# lcd_brd.net
KiCad netlist of a schematic drawn in EAGLE
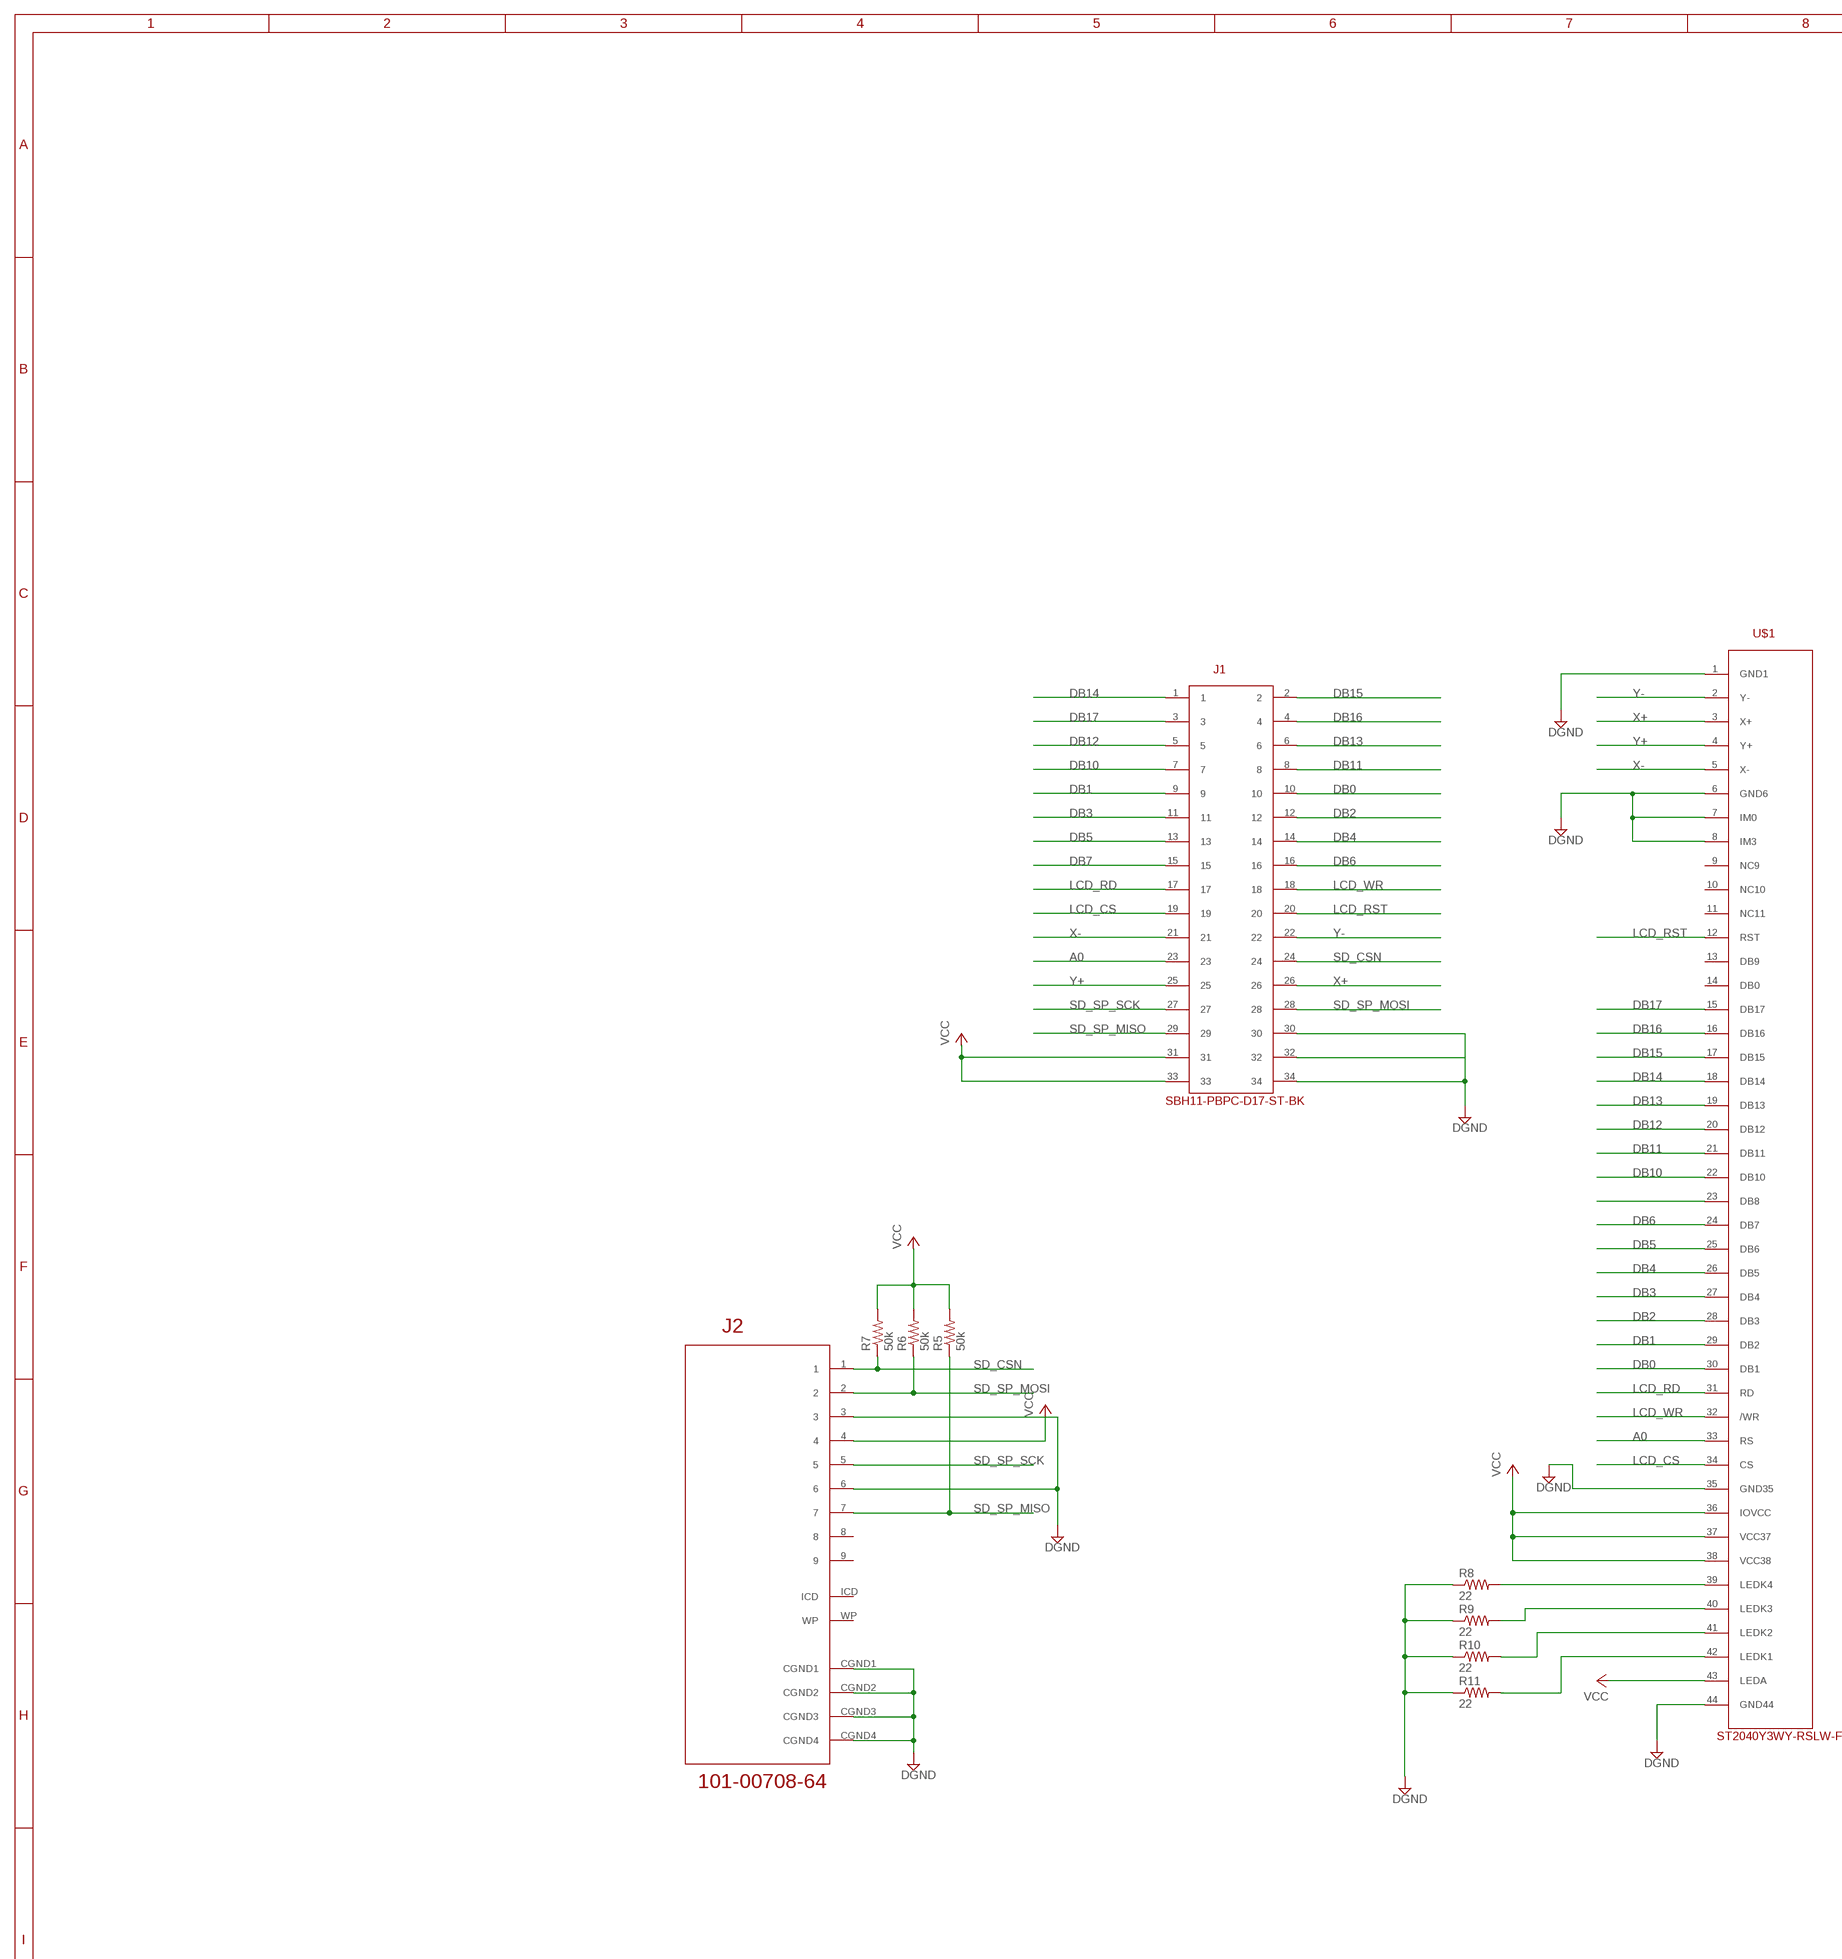
[diagram p0: schematic, sheet 1, part 1 of 2]
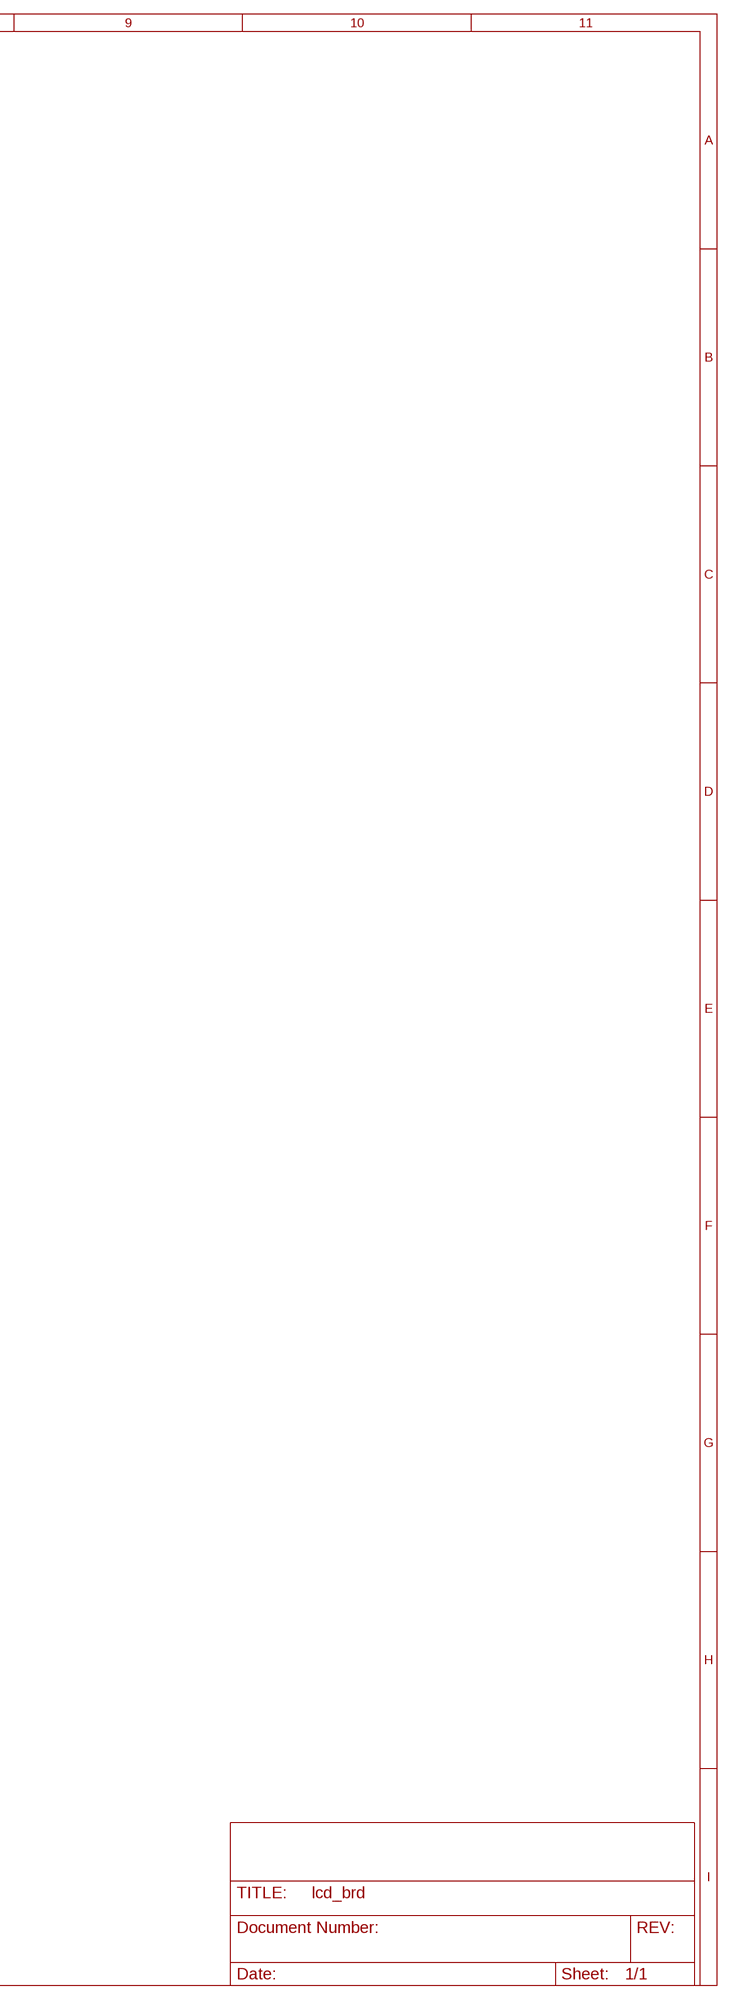
[diagram p1: schematic, sheet 1, part 2 of 2]

(export (version "E")
  (design (tool "Eeschema 10.0.6"))
  (components
    (comp (ref "J1")
      (value "SBH11-PBPC-D17-ST-BK")
      (footprint "eagle-import:SBH11-PBPC-D17-ST-BK")
      (libsource (lib "eagle-import") (part "SBH11-PBPC-D17-ST-BK"))
    )
    (comp (ref "J2")
      (value "101-00708-64")
      (footprint "eagle-import:101-00708-64")
      (libsource (lib "eagle-import") (part "101-00708-64"))
    )
    (comp (ref "R5")
      (value "50k")
      (footprint "eagle-import:R0603")
      (libsource (lib "eagle-import") (part "R-US_R0603"))
    )
    (comp (ref "R6")
      (value "50k")
      (footprint "eagle-import:R0603")
      (libsource (lib "eagle-import") (part "R-US_R0603"))
    )
    (comp (ref "R7")
      (value "50k")
      (footprint "eagle-import:R0603")
      (libsource (lib "eagle-import") (part "R-US_R0603"))
    )
    (comp (ref "R8")
      (value "22")
      (footprint "eagle-import:R0603")
      (libsource (lib "eagle-import") (part "R-US_R0603"))
    )
    (comp (ref "R9")
      (value "22")
      (footprint "eagle-import:R0603")
      (libsource (lib "eagle-import") (part "R-US_R0603"))
    )
    (comp (ref "R10")
      (value "22")
      (footprint "eagle-import:R0603")
      (libsource (lib "eagle-import") (part "R-US_R0603"))
    )
    (comp (ref "R11")
      (value "22")
      (footprint "eagle-import:R0603")
      (libsource (lib "eagle-import") (part "R-US_R0603"))
    )
    (comp (ref "U$1")
      (value "ST2040Y3WY-RSLW-F")
      (footprint "eagle-import:ST0240Y3WY-RSLW-F")
      (libsource (lib "eagle-import") (part "ST2040Y3WY-RSLW-F"))
    )
  )
  (nets
    (net (code "1") (name "/A0") (class "Default")
      (node (ref "J1") (pin "23") (pinfunction "23_23") (pintype "bidirectional"))
      (node (ref "U$1") (pin "33") (pinfunction "RS_33") (pintype "bidirectional"))
    )
    (net (code "2") (name "/DB0") (class "Default")
      (node (ref "J1") (pin "10") (pinfunction "10_10") (pintype "bidirectional"))
      (node (ref "U$1") (pin "30") (pinfunction "DB1_30") (pintype "bidirectional"))
    )
    (net (code "3") (name "/DB1") (class "Default")
      (node (ref "J1") (pin "9") (pinfunction "9_9") (pintype "bidirectional"))
      (node (ref "U$1") (pin "29") (pinfunction "DB2_29") (pintype "bidirectional"))
    )
    (net (code "4") (name "/DB2") (class "Default")
      (node (ref "J1") (pin "12") (pinfunction "12_12") (pintype "bidirectional"))
      (node (ref "U$1") (pin "28") (pinfunction "DB3_28") (pintype "bidirectional"))
    )
    (net (code "5") (name "/DB3") (class "Default")
      (node (ref "J1") (pin "11") (pinfunction "11_11") (pintype "bidirectional"))
      (node (ref "U$1") (pin "27") (pinfunction "DB4_27") (pintype "bidirectional"))
    )
    (net (code "6") (name "/DB4") (class "Default")
      (node (ref "J1") (pin "14") (pinfunction "14_14") (pintype "bidirectional"))
      (node (ref "U$1") (pin "26") (pinfunction "DB5_26") (pintype "bidirectional"))
    )
    (net (code "7") (name "/DB5") (class "Default")
      (node (ref "J1") (pin "13") (pinfunction "13_13") (pintype "bidirectional"))
      (node (ref "U$1") (pin "25") (pinfunction "DB6_25") (pintype "bidirectional"))
    )
    (net (code "8") (name "/DB6") (class "Default")
      (node (ref "J1") (pin "16") (pinfunction "16_16") (pintype "bidirectional"))
      (node (ref "U$1") (pin "24") (pinfunction "DB7_24") (pintype "bidirectional"))
    )
    (net (code "9") (name "/DB7") (class "Default")
      (node (ref "J1") (pin "15") (pinfunction "15_15") (pintype "bidirectional"))
      (node (ref "U$1") (pin "23") (pinfunction "DB8_23") (pintype "bidirectional"))
    )
    (net (code "10") (name "/DB10") (class "Default")
      (node (ref "J1") (pin "7") (pinfunction "7_7") (pintype "bidirectional"))
      (node (ref "U$1") (pin "22") (pinfunction "DB10_22") (pintype "bidirectional"))
    )
    (net (code "11") (name "/DB11") (class "Default")
      (node (ref "J1") (pin "8") (pinfunction "8_8") (pintype "bidirectional"))
      (node (ref "U$1") (pin "21") (pinfunction "DB11_21") (pintype "bidirectional"))
    )
    (net (code "12") (name "/DB12") (class "Default")
      (node (ref "J1") (pin "5") (pinfunction "5_5") (pintype "bidirectional"))
      (node (ref "U$1") (pin "20") (pinfunction "DB12_20") (pintype "bidirectional"))
    )
    (net (code "13") (name "/DB13") (class "Default")
      (node (ref "J1") (pin "6") (pinfunction "6_6") (pintype "bidirectional"))
      (node (ref "U$1") (pin "19") (pinfunction "DB13_19") (pintype "bidirectional"))
    )
    (net (code "14") (name "/DB14") (class "Default")
      (node (ref "J1") (pin "1") (pinfunction "1_1") (pintype "bidirectional"))
      (node (ref "U$1") (pin "18") (pinfunction "DB14_18") (pintype "bidirectional"))
    )
    (net (code "15") (name "/DB15") (class "Default")
      (node (ref "J1") (pin "2") (pinfunction "2_2") (pintype "bidirectional"))
      (node (ref "U$1") (pin "17") (pinfunction "DB15_17") (pintype "bidirectional"))
    )
    (net (code "16") (name "/DB16") (class "Default")
      (node (ref "J1") (pin "4") (pinfunction "4_4") (pintype "bidirectional"))
      (node (ref "U$1") (pin "16") (pinfunction "DB16_16") (pintype "bidirectional"))
    )
    (net (code "17") (name "/DB17") (class "Default")
      (node (ref "J1") (pin "3") (pinfunction "3_3") (pintype "bidirectional"))
      (node (ref "U$1") (pin "15") (pinfunction "DB17_15") (pintype "bidirectional"))
    )
    (net (code "18") (name "/LCD_CS") (class "Default")
      (node (ref "J1") (pin "19") (pinfunction "19_19") (pintype "bidirectional"))
      (node (ref "U$1") (pin "34") (pinfunction "CS_34") (pintype "bidirectional"))
    )
    (net (code "19") (name "/LCD_RD") (class "Default")
      (node (ref "J1") (pin "17") (pinfunction "17_17") (pintype "bidirectional"))
      (node (ref "U$1") (pin "31") (pinfunction "RD_31") (pintype "bidirectional"))
    )
    (net (code "20") (name "/LCD_RST") (class "Default")
      (node (ref "J1") (pin "20") (pinfunction "20_20") (pintype "bidirectional"))
      (node (ref "U$1") (pin "12") (pinfunction "RST_12") (pintype "bidirectional"))
    )
    (net (code "21") (name "/LCD_WR") (class "Default")
      (node (ref "J1") (pin "18") (pinfunction "18_18") (pintype "bidirectional"))
      (node (ref "U$1") (pin "32") (pinfunction "/WR_32") (pintype "bidirectional"))
    )
    (net (code "22") (name "/SD_CSN") (class "Default")
      (node (ref "J1") (pin "24") (pinfunction "24_24") (pintype "bidirectional"))
      (node (ref "J2") (pin "1") (pinfunction "1_1") (pintype "bidirectional"))
      (node (ref "R7") (pin "1") (pinfunction "1_1") (pintype "passive"))
    )
    (net (code "23") (name "/SD_SP_MISO") (class "Default")
      (node (ref "J1") (pin "29") (pinfunction "29_29") (pintype "bidirectional"))
      (node (ref "J2") (pin "7") (pinfunction "7_7") (pintype "bidirectional"))
      (node (ref "R5") (pin "1") (pinfunction "1_1") (pintype "passive"))
    )
    (net (code "24") (name "/SD_SP_MOSI") (class "Default")
      (node (ref "J1") (pin "28") (pinfunction "28_28") (pintype "bidirectional"))
      (node (ref "J2") (pin "2") (pinfunction "2_2") (pintype "bidirectional"))
      (node (ref "R6") (pin "1") (pinfunction "1_1") (pintype "passive"))
    )
    (net (code "25") (name "/SD_SP_SCK") (class "Default")
      (node (ref "J1") (pin "27") (pinfunction "27_27") (pintype "bidirectional"))
      (node (ref "J2") (pin "5") (pinfunction "5_5") (pintype "bidirectional"))
    )
    (net (code "26") (name "/X+") (class "Default")
      (node (ref "J1") (pin "26") (pinfunction "26_26") (pintype "bidirectional"))
      (node (ref "U$1") (pin "3") (pinfunction "X+_3") (pintype "bidirectional"))
    )
    (net (code "27") (name "/X-") (class "Default")
      (node (ref "J1") (pin "21") (pinfunction "21_21") (pintype "bidirectional"))
      (node (ref "U$1") (pin "5") (pinfunction "X-_5") (pintype "bidirectional"))
    )
    (net (code "28") (name "/Y+") (class "Default")
      (node (ref "J1") (pin "25") (pinfunction "25_25") (pintype "bidirectional"))
      (node (ref "U$1") (pin "4") (pinfunction "Y+_4") (pintype "bidirectional"))
    )
    (net (code "29") (name "/Y-") (class "Default")
      (node (ref "J1") (pin "22") (pinfunction "22_22") (pintype "bidirectional"))
      (node (ref "U$1") (pin "2") (pinfunction "Y-_2") (pintype "bidirectional"))
    )
    (net (code "30") (name "DGND") (class "Default")
      (node (ref "J1") (pin "30") (pinfunction "30_30") (pintype "bidirectional"))
      (node (ref "J1") (pin "32") (pinfunction "32_32") (pintype "bidirectional"))
      (node (ref "J1") (pin "34") (pinfunction "34_34") (pintype "bidirectional"))
      (node (ref "J2") (pin "3") (pinfunction "3_3") (pintype "bidirectional"))
      (node (ref "J2") (pin "6") (pinfunction "6_6") (pintype "bidirectional"))
      (node (ref "J2") (pin "CGND1") (pinfunction "CGND1_CGND1") (pintype "bidirectional"))
      (node (ref "J2") (pin "CGND2") (pinfunction "CGND2_CGND2") (pintype "bidirectional"))
      (node (ref "J2") (pin "CGND3") (pinfunction "CGND3_CGND3") (pintype "bidirectional"))
      (node (ref "J2") (pin "CGND4") (pinfunction "CGND4_CGND4") (pintype "bidirectional"))
      (node (ref "R10") (pin "1") (pinfunction "1_1") (pintype "passive"))
      (node (ref "R11") (pin "1") (pinfunction "1_1") (pintype "passive"))
      (node (ref "R8") (pin "1") (pinfunction "1_1") (pintype "passive"))
      (node (ref "R9") (pin "1") (pinfunction "1_1") (pintype "passive"))
      (node (ref "U$1") (pin "1") (pinfunction "GND1_1") (pintype "bidirectional"))
      (node (ref "U$1") (pin "35") (pinfunction "GND35_35") (pintype "bidirectional"))
      (node (ref "U$1") (pin "44") (pinfunction "GND44_44") (pintype "bidirectional"))
      (node (ref "U$1") (pin "6") (pinfunction "GND6_6") (pintype "bidirectional"))
      (node (ref "U$1") (pin "7") (pinfunction "IM0_7") (pintype "bidirectional"))
      (node (ref "U$1") (pin "8") (pinfunction "IM3_8") (pintype "bidirectional"))
    )
    (net (code "31") (name "Net-(U$1-LEDK1)") (class "Default")
      (node (ref "R11") (pin "2") (pinfunction "2_2") (pintype "passive"))
      (node (ref "U$1") (pin "42") (pinfunction "LEDK1_42") (pintype "bidirectional"))
    )
    (net (code "32") (name "Net-(U$1-LEDK2)") (class "Default")
      (node (ref "R10") (pin "2") (pinfunction "2_2") (pintype "passive"))
      (node (ref "U$1") (pin "41") (pinfunction "LEDK2_41") (pintype "bidirectional"))
    )
    (net (code "33") (name "Net-(U$1-LEDK3)") (class "Default")
      (node (ref "R9") (pin "2") (pinfunction "2_2") (pintype "passive"))
      (node (ref "U$1") (pin "40") (pinfunction "LEDK3_40") (pintype "bidirectional"))
    )
    (net (code "34") (name "Net-(U$1-LEDK4)") (class "Default")
      (node (ref "R8") (pin "2") (pinfunction "2_2") (pintype "passive"))
      (node (ref "U$1") (pin "39") (pinfunction "LEDK4_39") (pintype "bidirectional"))
    )
    (net (code "35") (name "VCC") (class "Default")
      (node (ref "J1") (pin "31") (pinfunction "31_31") (pintype "bidirectional"))
      (node (ref "J1") (pin "33") (pinfunction "33_33") (pintype "bidirectional"))
      (node (ref "J2") (pin "4") (pinfunction "4_4") (pintype "bidirectional"))
      (node (ref "R5") (pin "2") (pinfunction "2_2") (pintype "passive"))
      (node (ref "R6") (pin "2") (pinfunction "2_2") (pintype "passive"))
      (node (ref "R7") (pin "2") (pinfunction "2_2") (pintype "passive"))
      (node (ref "U$1") (pin "36") (pinfunction "IOVCC_36") (pintype "bidirectional"))
      (node (ref "U$1") (pin "37") (pinfunction "VCC37_37") (pintype "bidirectional"))
      (node (ref "U$1") (pin "38") (pinfunction "VCC38_38") (pintype "bidirectional"))
      (node (ref "U$1") (pin "43") (pinfunction "LEDA_43") (pintype "bidirectional"))
    )
    (net (code "36") (name "unconnected-(J2-Pad8)") (class "Default")
      (node (ref "J2") (pin "8") (pinfunction "8_8") (pintype "bidirectional"))
    )
    (net (code "37") (name "unconnected-(J2-Pad9)") (class "Default")
      (node (ref "J2") (pin "9") (pinfunction "9_9") (pintype "bidirectional"))
    )
    (net (code "38") (name "unconnected-(J2-PadICD)") (class "Default")
      (node (ref "J2") (pin "ICD") (pinfunction "ICD_ICD") (pintype "bidirectional"))
    )
    (net (code "39") (name "unconnected-(J2-PadWP)") (class "Default")
      (node (ref "J2") (pin "WP") (pinfunction "WP_WP") (pintype "bidirectional"))
    )
    (net (code "40") (name "unconnected-(U$1-DB0-Pad14)") (class "Default")
      (node (ref "U$1") (pin "14") (pinfunction "DB0_14") (pintype "bidirectional"))
    )
    (net (code "41") (name "unconnected-(U$1-DB9-Pad13)") (class "Default")
      (node (ref "U$1") (pin "13") (pinfunction "DB9_13") (pintype "bidirectional"))
    )
    (net (code "42") (name "unconnected-(U$1-NC9-Pad9)") (class "Default")
      (node (ref "U$1") (pin "9") (pinfunction "NC9_9") (pintype "bidirectional"))
    )
    (net (code "43") (name "unconnected-(U$1-NC10-Pad10)") (class "Default")
      (node (ref "U$1") (pin "10") (pinfunction "NC10_10") (pintype "bidirectional"))
    )
    (net (code "44") (name "unconnected-(U$1-NC11-Pad11)") (class "Default")
      (node (ref "U$1") (pin "11") (pinfunction "NC11_11") (pintype "bidirectional"))
    )
  )
)
